# led_chaser.net
KiCad netlist of a schematic drawn in Altium Designer
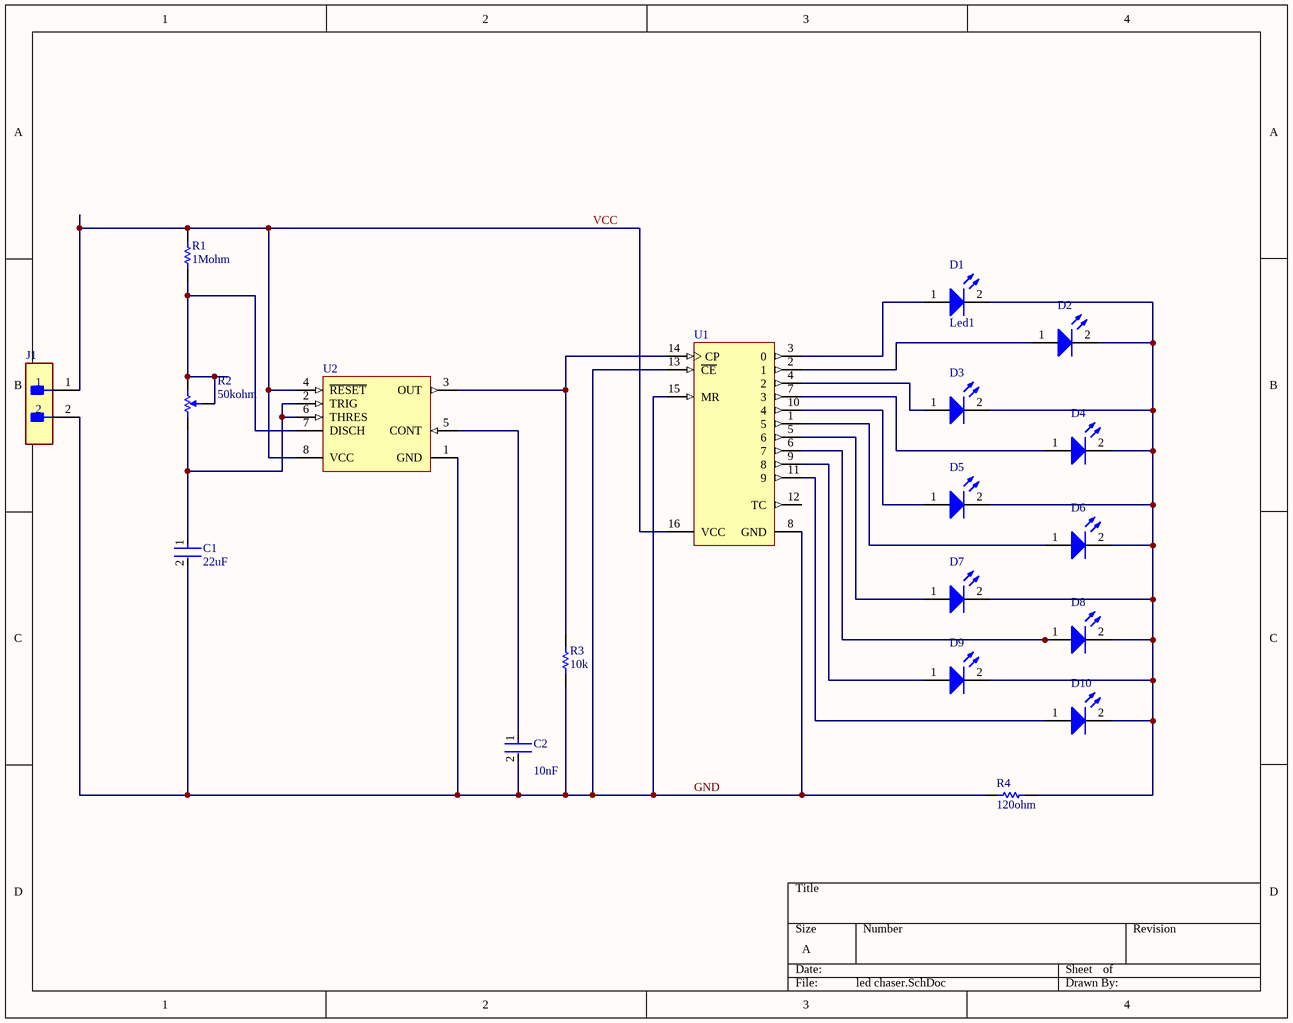
[diagram p0: led chaser.SchDoc]

(export (version "E")
  (design (tool "Eeschema 10.0.6"))
  (components
    (comp (ref "C1")
      (value "RCER71E106K3M1H03A")
      (footprint "FP-RCE3M1-MFG")
      (description "Cap Ceramic 10uF 25V X7R ±10% Radial 5mm +125°C Automotive Ammo Pack")
      (fields (field (name "TOLERANCE") "10%") (field (name "CAPACITANCE") "22uF"))
      (libsource (lib "Altium Content Vault") (part "02cd4be3c70576c341d710602a673aa"))
    )
    (comp (ref "C2")
      (value "RCER71E106K3M1H03A")
      (footprint "FP-RCE3M1-MFG")
      (description "Cap Ceramic 10uF 25V X7R ±10% Radial 5mm +125°C Automotive Ammo Pack")
      (fields (field (name "TOLERANCE") "10%") (field (name "CAPACITANCE") "10nF"))
      (libsource (lib "Altium Content Vault") (part "02cd4be3c70576c341d710602a673aa"))
    )
    (comp (ref "D1")
      (value "Led1")
      (footprint "WL-TMRC_D5.9H8.7")
      (libsource (lib "Altium Content Vault") (part "LED_Blue_1A-2K"))
    )
    (comp (ref "D2")
      (value "Led6")
      (footprint "WL-TMRC_D5.9H8.7")
      (libsource (lib "Altium Content Vault") (part "LED_Blue_1A-2K"))
    )
    (comp (ref "D3")
      (value "2")
      (footprint "WL-TMRC_D5.9H8.7")
      (libsource (lib "Altium Content Vault") (part "LED_Blue_1A-2K"))
    )
    (comp (ref "D4")
      (value "Led7")
      (footprint "WL-TMRC_D5.9H8.7")
      (libsource (lib "Altium Content Vault") (part "LED_Blue_1A-2K"))
    )
    (comp (ref "D5")
      (value "Led3")
      (footprint "WL-TMRC_D5.9H8.7")
      (libsource (lib "Altium Content Vault") (part "LED_Blue_1A-2K"))
    )
    (comp (ref "D6")
      (value "Led8")
      (footprint "WL-TMRC_D5.9H8.7")
      (libsource (lib "Altium Content Vault") (part "LED_Blue_1A-2K"))
    )
    (comp (ref "D7")
      (value "Led4")
      (footprint "WL-TMRC_D5.9H8.7")
      (libsource (lib "Altium Content Vault") (part "LED_Blue_1A-2K"))
    )
    (comp (ref "D8")
      (value "Led9")
      (footprint "WL-TMRC_D5.9H8.7")
      (libsource (lib "Altium Content Vault") (part "LED_Blue_1A-2K"))
    )
    (comp (ref "D9")
      (value "Led5")
      (footprint "WL-TMRC_D5.9H8.7")
      (libsource (lib "Altium Content Vault") (part "LED_Blue_1A-2K"))
    )
    (comp (ref "D10")
      (value "Led10")
      (footprint "WL-TMRC_D5.9H8.7")
      (libsource (lib "Altium Content Vault") (part "LED_Blue_1A-2K"))
    )
    (comp (ref "J1")
      (value "M20-9990246")
      (footprint "FP-M20-9990246-MFG")
      (description "Connector Header Through Hole 2 position 0.100\" (2.54mm)")
      (fields (field (name "OCTOPART") "https://octopart.com/m20-9990246-harwin-2590635"))
      (libsource (lib "Altium Content Vault") (part "3bc925449376181038e59eaffc5286c"))
    )
    (comp (ref "R1")
      (value "MFR-25FBF52-1M")
      (footprint "RESA60-630X240")
      (description "Axial Resistor, 1 MOhm, +/- 1%, 250 mW, -55 to 155 degC, 2-Pin THD, RoHS, Bulk")
      (fields (field (name "RESISTANCE") "1Mohm") (field (name "TOLERANCE") "1%"))
      (libsource (lib "Altium Content Vault") (part "RES-2"))
    )
    (comp (ref "R2")
      (value "50kohm")
      (footprint "BOUR-3313J-1_V")
      (fields (field (name "MANUFACTURER") "Bourns"))
      (libsource (lib "Altium Content Vault") (part "RES-ADJ-3_A"))
    )
    (comp (ref "R3")
      (value "10k")
      (footprint "OMTE-RES7X2.5-2")
      (fields
        (field (name "TOLERANCE") "±5%")
        (field (name "PARTNUMBER") "OD103JE")
        (field (name "MANUFACTURER") "Ohmite")
      )
      (libsource (lib "Altium Content Vault") (part "RES-2"))
    )
    (comp (ref "R4")
      (value "120ohm")
      (footprint "OMTE-RES7X2.5-2")
      (fields
        (field (name "TOLERANCE") "±5%")
        (field (name "PARTNUMBER") "OD103JE")
        (field (name "MANUFACTURER") "Ohmite")
      )
      (libsource (lib "Altium Content Vault") (part "RES-2"))
    )
    (comp (ref "U1")
      (value "CD74HC4017E")
      (footprint "N0016A")
      (description "High Speed CMOS Logic Decade Counter/Divider with 10 Decoded Outputs, N0016A, TUBE")
      (fields
        (field (name "GENERIC PART NUMBER") "CD74HC4017")
        (field (name "MANUFACTURER") "Texas Instruments")
      )
      (libsource (lib "Altium Content Vault") (part "TI-CD74HC4017-16"))
    )
    (comp (ref "U2")
      (value "NE555P")
      (footprint "P0008A")
      (description "Precision Timer, 4.5 to 16 V, 0 to 70 degC, 8-Pin DIP, Pb-Free, Tube")
      (fields (field (name "MANUFACTURER") "TexasInstruments"))
      (libsource (lib "Altium Content Vault") (part "TI-NE555-P8"))
    )
  )
  (nets
    (net (code "1") (name "/GND") (class "Default")
      (node (ref "C1") (pin "2") (pinfunction "2_2") (pintype "passive"))
      (node (ref "C2") (pin "2") (pinfunction "2_2") (pintype "passive"))
      (node (ref "J1") (pin "2") (pinfunction "2_2") (pintype "passive"))
      (node (ref "R3") (pin "1") (pinfunction "1_1") (pintype "passive"))
      (node (ref "R4") (pin "1") (pinfunction "1_1") (pintype "passive"))
      (node (ref "U1") (pin "13") (pinfunction "~{CE}_13") (pintype "input"))
      (node (ref "U1") (pin "15") (pinfunction "MR_15") (pintype "input"))
      (node (ref "U1") (pin "8") (pinfunction "GND_8") (pintype "power_in"))
      (node (ref "U2") (pin "1") (pinfunction "GND_1") (pintype "power_in"))
    )
    (net (code "2") (name "/VCC") (class "Default")
      (node (ref "J1") (pin "1") (pinfunction "1_1") (pintype "passive"))
      (node (ref "R1") (pin "2") (pinfunction "2_2") (pintype "passive"))
      (node (ref "U1") (pin "16") (pinfunction "VCC_16") (pintype "power_in"))
      (node (ref "U2") (pin "4") (pinfunction "~{RESET}_4") (pintype "input"))
      (node (ref "U2") (pin "8") (pinfunction "VCC_8") (pintype "power_in"))
    )
    (net (code "3") (name "Net-(D1-A)") (class "Default")
      (node (ref "D1") (pin "1") (pinfunction "A_1") (pintype "passive"))
      (node (ref "U1") (pin "3") (pinfunction "0_3") (pintype "output"))
    )
    (net (code "4") (name "Net-(D1-K)") (class "Default")
      (node (ref "D1") (pin "2") (pinfunction "K_2") (pintype "passive"))
      (node (ref "D10") (pin "2") (pinfunction "K_2") (pintype "passive"))
      (node (ref "D2") (pin "2") (pinfunction "K_2") (pintype "passive"))
      (node (ref "D3") (pin "2") (pinfunction "K_2") (pintype "passive"))
      (node (ref "D4") (pin "2") (pinfunction "K_2") (pintype "passive"))
      (node (ref "D5") (pin "2") (pinfunction "K_2") (pintype "passive"))
      (node (ref "D6") (pin "2") (pinfunction "K_2") (pintype "passive"))
      (node (ref "D7") (pin "2") (pinfunction "K_2") (pintype "passive"))
      (node (ref "D8") (pin "2") (pinfunction "K_2") (pintype "passive"))
      (node (ref "D9") (pin "2") (pinfunction "K_2") (pintype "passive"))
      (node (ref "R4") (pin "2") (pinfunction "2_2") (pintype "passive"))
    )
    (net (code "5") (name "Net-(D2-A)") (class "Default")
      (node (ref "D2") (pin "1") (pinfunction "A_1") (pintype "passive"))
      (node (ref "U1") (pin "2") (pinfunction "1_2") (pintype "output"))
    )
    (net (code "6") (name "Net-(D3-A)") (class "Default")
      (node (ref "D3") (pin "1") (pinfunction "A_1") (pintype "passive"))
      (node (ref "U1") (pin "4") (pinfunction "2_4") (pintype "output"))
    )
    (net (code "7") (name "Net-(D4-A)") (class "Default")
      (node (ref "D4") (pin "1") (pinfunction "A_1") (pintype "passive"))
      (node (ref "U1") (pin "7") (pinfunction "3_7") (pintype "output"))
    )
    (net (code "8") (name "Net-(D5-A)") (class "Default")
      (node (ref "D5") (pin "1") (pinfunction "A_1") (pintype "passive"))
      (node (ref "U1") (pin "10") (pinfunction "4_10") (pintype "output"))
    )
    (net (code "9") (name "Net-(D6-A)") (class "Default")
      (node (ref "D6") (pin "1") (pinfunction "A_1") (pintype "passive"))
      (node (ref "U1") (pin "1") (pinfunction "5_1") (pintype "output"))
    )
    (net (code "10") (name "Net-(D7-A)") (class "Default")
      (node (ref "D7") (pin "1") (pinfunction "A_1") (pintype "passive"))
      (node (ref "U1") (pin "5") (pinfunction "6_5") (pintype "output"))
    )
    (net (code "11") (name "Net-(D8-A)") (class "Default")
      (node (ref "D8") (pin "1") (pinfunction "A_1") (pintype "passive"))
      (node (ref "U1") (pin "6") (pinfunction "7_6") (pintype "output"))
    )
    (net (code "12") (name "Net-(D9-A)") (class "Default")
      (node (ref "D9") (pin "1") (pinfunction "A_1") (pintype "passive"))
      (node (ref "U1") (pin "9") (pinfunction "8_9") (pintype "output"))
    )
    (net (code "13") (name "Net-(D10-A)") (class "Default")
      (node (ref "D10") (pin "1") (pinfunction "A_1") (pintype "passive"))
      (node (ref "U1") (pin "11") (pinfunction "9_11") (pintype "output"))
    )
    (net (code "14") (name "Net-(U1-CP)") (class "Default")
      (node (ref "R3") (pin "2") (pinfunction "2_2") (pintype "passive"))
      (node (ref "U1") (pin "14") (pinfunction "CP_14") (pintype "input"))
      (node (ref "U2") (pin "3") (pinfunction "OUT_3") (pintype "output"))
    )
    (net (code "15") (name "Net-(U2-CONT)") (class "Default")
      (node (ref "C2") (pin "1") (pinfunction "1_1") (pintype "passive"))
      (node (ref "U2") (pin "5") (pinfunction "CONT_5") (pintype "input"))
    )
    (net (code "16") (name "Net-(U2-DISCH)") (class "Default")
      (node (ref "R1") (pin "1") (pinfunction "1_1") (pintype "passive"))
      (node (ref "R2") (pin "2") (pinfunction "2_2") (pintype "passive"))
      (node (ref "R2") (pin "3") (pinfunction "3_3") (pintype "passive"))
      (node (ref "U2") (pin "7") (pinfunction "DISCH_7") (pintype "open_collector"))
    )
    (net (code "17") (name "Net-(U2-THRES)") (class "Default")
      (node (ref "C1") (pin "1") (pinfunction "1_1") (pintype "passive"))
      (node (ref "R2") (pin "1") (pinfunction "1_1") (pintype "passive"))
      (node (ref "U2") (pin "2") (pinfunction "TRIG_2") (pintype "input"))
      (node (ref "U2") (pin "6") (pinfunction "THRES_6") (pintype "input"))
    )
    (net (code "18") (name "unconnected-(U1-TC-Pad12)") (class "Default")
      (node (ref "U1") (pin "12") (pinfunction "TC_12") (pintype "output"))
    )
  )
)
